# remote_V0_04.net
KiCad netlist of a schematic drawn in EAGLE
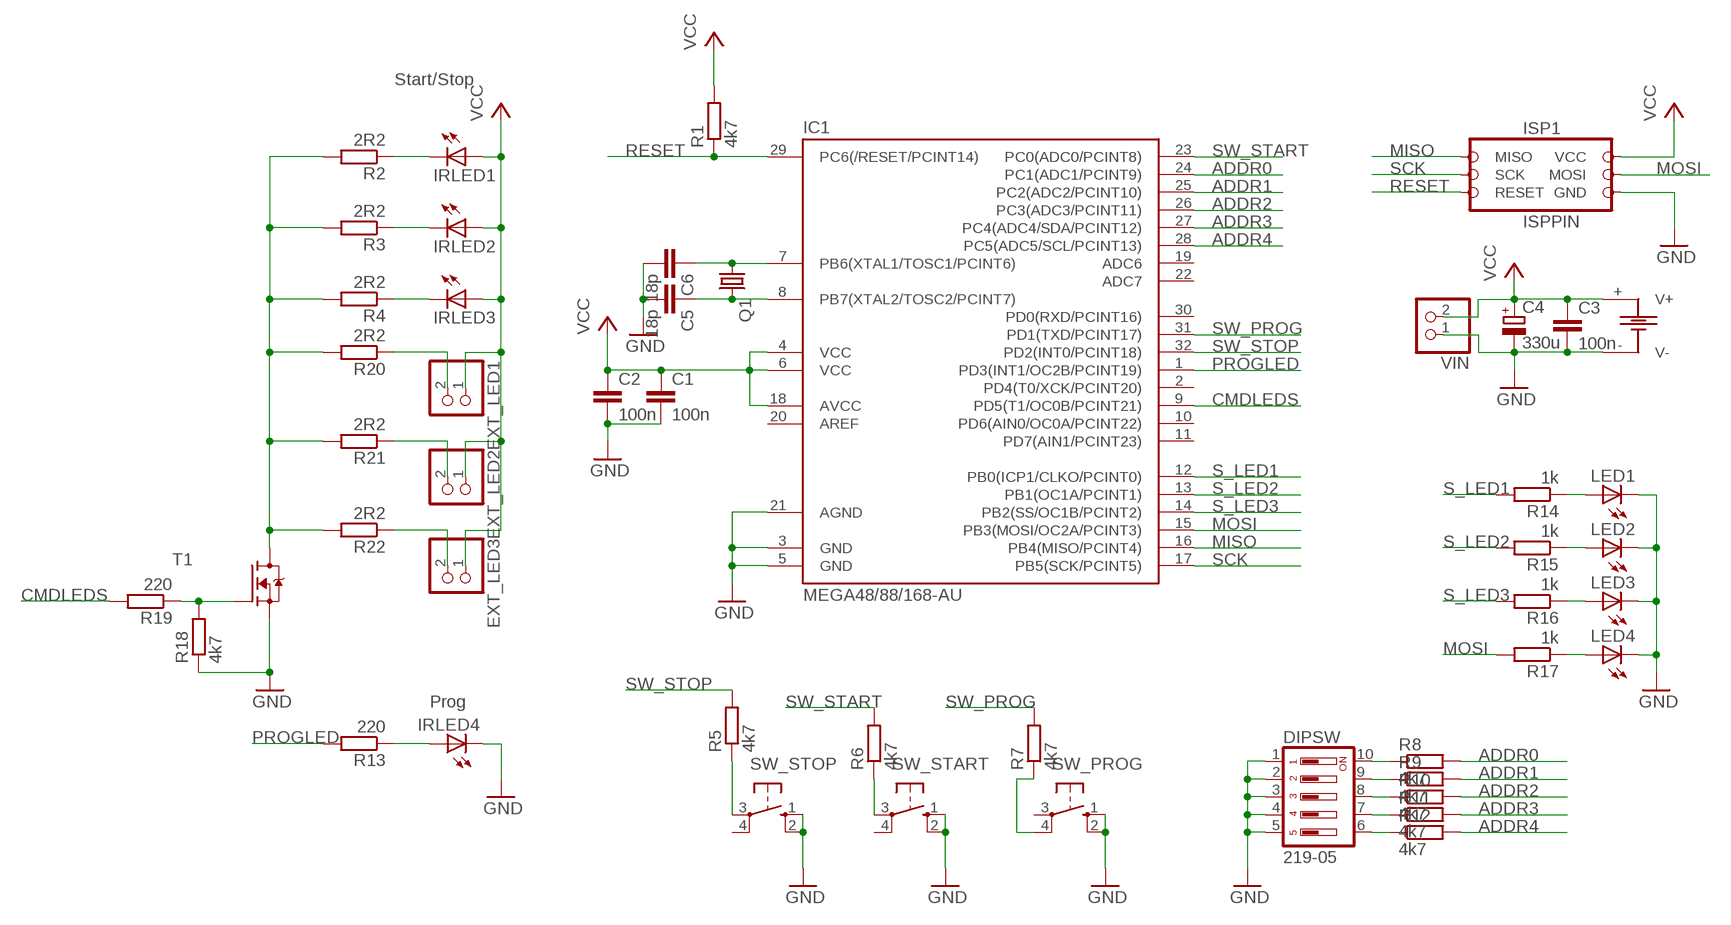
[diagram p0: schematic, sheet 1]

(export (version "E")
  (design (tool "Eeschema 10.0.6"))
  (components
    (comp (ref "B1")
      (value "BATTERY_HOLDER_1")
      (footprint "eagle-import:BAT_HOLDER_1")
      (libsource (lib "eagle-import") (part "BATTERY_HOLDER_1"))
    )
    (comp (ref "C1")
      (value "100n")
      (footprint "eagle-import:C0805WP")
      (libsource (lib "eagle-import") (part "C-EUC0805WP"))
    )
    (comp (ref "C2")
      (value "100n")
      (footprint "eagle-import:C0805WP")
      (libsource (lib "eagle-import") (part "C-EUC0805WP"))
    )
    (comp (ref "C3")
      (value "100n")
      (footprint "eagle-import:C0805WP")
      (libsource (lib "eagle-import") (part "C-EUC0805WP"))
    )
    (comp (ref "C4")
      (value "330u")
      (footprint "eagle-import:SANYO-OSCON_SMD_C6")
      (libsource (lib "eagle-import") (part "CPOL-EUSANYO_SMD_C6"))
    )
    (comp (ref "C5")
      (value "18p")
      (footprint "eagle-import:C0805WP")
      (libsource (lib "eagle-import") (part "C-EUC0805WP"))
    )
    (comp (ref "C6")
      (value "18p")
      (footprint "eagle-import:C0805WP")
      (libsource (lib "eagle-import") (part "C-EUC0805WP"))
    )
    (comp (ref "DIPSW")
      (value "219-05")
      (footprint "eagle-import:CTS-219-05")
      (libsource (lib "eagle-import") (part "219-05"))
    )
    (comp (ref "EXT_LED1")
      (value "PINHD-1X2LONG")
      (footprint "eagle-import:1X2LONG")
      (libsource (lib "eagle-import") (part "PINHD-1X2LONG"))
    )
    (comp (ref "EXT_LED2")
      (value "PINHD-1X2LONG")
      (footprint "eagle-import:1X2LONG")
      (libsource (lib "eagle-import") (part "PINHD-1X2LONG"))
    )
    (comp (ref "EXT_LED3")
      (value "PINHD-1X2LONG")
      (footprint "eagle-import:1X2LONG")
      (libsource (lib "eagle-import") (part "PINHD-1X2LONG"))
    )
    (comp (ref "IC1")
      (value "MEGA48/88/168-AU")
      (footprint "eagle-import:TQFP32-08")
      (libsource (lib "eagle-import") (part "MEGA48/88/168-AU"))
    )
    (comp (ref "IRLED1")
      (value "LEDLED5MMH")
      (footprint "eagle-import:LED5MMH")
      (libsource (lib "eagle-import") (part "LEDLED5MMH"))
    )
    (comp (ref "IRLED2")
      (value "LEDLED5MMH")
      (footprint "eagle-import:LED5MMH")
      (libsource (lib "eagle-import") (part "LEDLED5MMH"))
    )
    (comp (ref "IRLED3")
      (value "LEDLED5MMH")
      (footprint "eagle-import:LED5MMH")
      (libsource (lib "eagle-import") (part "LEDLED5MMH"))
    )
    (comp (ref "IRLED4")
      (value "LEDLED5MMH")
      (footprint "eagle-import:LED5MMH")
      (libsource (lib "eagle-import") (part "LEDLED5MMH"))
    )
    (comp (ref "ISP1")
      (value "ISPPIN")
      (footprint "eagle-import:2X03")
      (libsource (lib "eagle-import") (part "ISPPIN"))
    )
    (comp (ref "LED1")
      (value "LED0805")
      (footprint "eagle-import:LED_0805")
      (libsource (lib "eagle-import") (part "LED0805"))
    )
    (comp (ref "LED2")
      (value "LED0805")
      (footprint "eagle-import:LED_0805")
      (libsource (lib "eagle-import") (part "LED0805"))
    )
    (comp (ref "LED3")
      (value "LED0805")
      (footprint "eagle-import:LED_0805")
      (libsource (lib "eagle-import") (part "LED0805"))
    )
    (comp (ref "LED4")
      (value "LED0805")
      (footprint "eagle-import:LED_0805")
      (libsource (lib "eagle-import") (part "LED0805"))
    )
    (comp (ref "Q1")
      (value "CRYSTALHC49S")
      (footprint "eagle-import:HC49_S")
      (libsource (lib "eagle-import") (part "CRYSTALHC49S"))
    )
    (comp (ref "R1")
      (value "4k7")
      (footprint "eagle-import:R0805WP")
      (libsource (lib "eagle-import") (part "R-EU_R0805WP"))
    )
    (comp (ref "R2")
      (value "2R2")
      (footprint "eagle-import:R0805WP")
      (libsource (lib "eagle-import") (part "R-EU_R0805WP"))
    )
    (comp (ref "R3")
      (value "2R2")
      (footprint "eagle-import:R0805WP")
      (libsource (lib "eagle-import") (part "R-EU_R0805WP"))
    )
    (comp (ref "R4")
      (value "2R2")
      (footprint "eagle-import:R0805WP")
      (libsource (lib "eagle-import") (part "R-EU_R0805WP"))
    )
    (comp (ref "R5")
      (value "4k7")
      (footprint "eagle-import:R0805WP")
      (libsource (lib "eagle-import") (part "R-EU_R0805WP"))
    )
    (comp (ref "R6")
      (value "4k7")
      (footprint "eagle-import:R0805WP")
      (libsource (lib "eagle-import") (part "R-EU_R0805WP"))
    )
    (comp (ref "R7")
      (value "4k7")
      (footprint "eagle-import:R0805WP")
      (libsource (lib "eagle-import") (part "R-EU_R0805WP"))
    )
    (comp (ref "R8")
      (value "4k7")
      (footprint "eagle-import:R0805WP")
      (libsource (lib "eagle-import") (part "R-EU_R0805WP"))
    )
    (comp (ref "R9")
      (value "4k7")
      (footprint "eagle-import:R0805WP")
      (libsource (lib "eagle-import") (part "R-EU_R0805WP"))
    )
    (comp (ref "R10")
      (value "4k7")
      (footprint "eagle-import:R0805WP")
      (libsource (lib "eagle-import") (part "R-EU_R0805WP"))
    )
    (comp (ref "R11")
      (value "4k7")
      (footprint "eagle-import:R0805WP")
      (libsource (lib "eagle-import") (part "R-EU_R0805WP"))
    )
    (comp (ref "R12")
      (value "4k7")
      (footprint "eagle-import:R0805WP")
      (libsource (lib "eagle-import") (part "R-EU_R0805WP"))
    )
    (comp (ref "R13")
      (value "220")
      (footprint "eagle-import:R0805WP")
      (libsource (lib "eagle-import") (part "R-EU_R0805WP"))
    )
    (comp (ref "R14")
      (value "1k")
      (footprint "eagle-import:R0805WP")
      (libsource (lib "eagle-import") (part "R-EU_R0805WP"))
    )
    (comp (ref "R15")
      (value "1k")
      (footprint "eagle-import:R0805WP")
      (libsource (lib "eagle-import") (part "R-EU_R0805WP"))
    )
    (comp (ref "R16")
      (value "1k")
      (footprint "eagle-import:R0805WP")
      (libsource (lib "eagle-import") (part "R-EU_R0805WP"))
    )
    (comp (ref "R17")
      (value "1k")
      (footprint "eagle-import:R0805WP")
      (libsource (lib "eagle-import") (part "R-EU_R0805WP"))
    )
    (comp (ref "R18")
      (value "4k7")
      (footprint "eagle-import:R0805WP")
      (libsource (lib "eagle-import") (part "R-EU_R0805WP"))
    )
    (comp (ref "R19")
      (value "220")
      (footprint "eagle-import:R0805WP")
      (libsource (lib "eagle-import") (part "R-EU_R0805WP"))
    )
    (comp (ref "R20")
      (value "2R2")
      (footprint "eagle-import:R0805WP")
      (libsource (lib "eagle-import") (part "R-EU_R0805WP"))
    )
    (comp (ref "R21")
      (value "2R2")
      (footprint "eagle-import:R0805WP")
      (libsource (lib "eagle-import") (part "R-EU_R0805WP"))
    )
    (comp (ref "R22")
      (value "2R2")
      (footprint "eagle-import:R0805WP")
      (libsource (lib "eagle-import") (part "R-EU_R0805WP"))
    )
    (comp (ref "SW_PROG")
      (value "10-XX")
      (footprint "eagle-import:B3F-10XX")
      (fields (field (name "MPN") "B3F-1000"))
      (libsource (lib "eagle-import") (part "10-XX"))
    )
    (comp (ref "SW_START")
      (value "10-XX")
      (footprint "eagle-import:B3F-10XX")
      (fields (field (name "MPN") "B3F-1000"))
      (libsource (lib "eagle-import") (part "10-XX"))
    )
    (comp (ref "SW_STOP")
      (value "10-XX")
      (footprint "eagle-import:B3F-10XX")
      (fields (field (name "MPN") "B3F-1000"))
      (libsource (lib "eagle-import") (part "10-XX"))
    )
    (comp (ref "T1")
      (value "MOSFET_N_SOT23")
      (footprint "eagle-import:SOT23")
      (libsource (lib "eagle-import") (part "MOSFET_N_SOT23"))
    )
    (comp (ref "VIN")
      (value "PINHD-1X2")
      (footprint "eagle-import:1X02")
      (libsource (lib "eagle-import") (part "pinhead_PINHD-1X2"))
    )
  )
  (nets
    (net (code "1") (name "/ADDR0") (class "Default")
      (node (ref "IC1") (pin "24") (pinfunction "PC1(ADC1/PCINT9)_24") (pintype "bidirectional"))
      (node (ref "R8") (pin "2") (pinfunction "2_2") (pintype "passive"))
    )
    (net (code "2") (name "/ADDR1") (class "Default")
      (node (ref "IC1") (pin "25") (pinfunction "PC2(ADC2/PCINT10)_25") (pintype "bidirectional"))
      (node (ref "R9") (pin "2") (pinfunction "2_2") (pintype "passive"))
    )
    (net (code "3") (name "/ADDR2") (class "Default")
      (node (ref "IC1") (pin "26") (pinfunction "PC3(ADC3/PCINT11)_26") (pintype "bidirectional"))
      (node (ref "R10") (pin "2") (pinfunction "2_2") (pintype "passive"))
    )
    (net (code "4") (name "/ADDR3") (class "Default")
      (node (ref "IC1") (pin "27") (pinfunction "PC4(ADC4/SDA/PCINT12)_27") (pintype "bidirectional"))
      (node (ref "R11") (pin "2") (pinfunction "2_2") (pintype "passive"))
    )
    (net (code "5") (name "/ADDR4") (class "Default")
      (node (ref "IC1") (pin "28") (pinfunction "PC5(ADC5/SCL/PCINT13)_28") (pintype "bidirectional"))
      (node (ref "R12") (pin "2") (pinfunction "2_2") (pintype "passive"))
    )
    (net (code "6") (name "/CMDLEDS") (class "Default")
      (node (ref "IC1") (pin "9") (pinfunction "PD5(T1/OC0B/PCINT21)_9") (pintype "bidirectional"))
      (node (ref "R19") (pin "2") (pinfunction "2_2") (pintype "passive"))
    )
    (net (code "7") (name "/MISO") (class "Default")
      (node (ref "IC1") (pin "16") (pinfunction "PB4(MISO/PCINT4)_16") (pintype "bidirectional"))
      (node (ref "ISP1") (pin "1") (pinfunction "MISO_1") (pintype "passive"))
    )
    (net (code "8") (name "/MOSI") (class "Default")
      (node (ref "IC1") (pin "15") (pinfunction "PB3(MOSI/OC2A/PCINT3)_15") (pintype "bidirectional"))
      (node (ref "ISP1") (pin "4") (pinfunction "MOSI_4") (pintype "passive"))
      (node (ref "R17") (pin "2") (pinfunction "2_2") (pintype "passive"))
    )
    (net (code "9") (name "/PROGLED") (class "Default")
      (node (ref "IC1") (pin "1") (pinfunction "PD3(INT1/OC2B/PCINT19)_1") (pintype "bidirectional"))
      (node (ref "R13") (pin "2") (pinfunction "2_2") (pintype "passive"))
    )
    (net (code "10") (name "/RESET") (class "Default")
      (node (ref "IC1") (pin "29") (pinfunction "PC6(/RESET/PCINT14)_29") (pintype "bidirectional"))
      (node (ref "ISP1") (pin "5") (pinfunction "RESET_5") (pintype "passive"))
      (node (ref "R1") (pin "1") (pinfunction "1_1") (pintype "passive"))
    )
    (net (code "11") (name "/SCK") (class "Default")
      (node (ref "IC1") (pin "17") (pinfunction "PB5(SCK/PCINT5)_17") (pintype "bidirectional"))
      (node (ref "ISP1") (pin "3") (pinfunction "SCK_3") (pintype "passive"))
    )
    (net (code "12") (name "/SW_PROG") (class "Default")
      (node (ref "IC1") (pin "31") (pinfunction "PD1(TXD/PCINT17)_31") (pintype "bidirectional"))
      (node (ref "R7") (pin "2") (pinfunction "2_2") (pintype "passive"))
    )
    (net (code "13") (name "/SW_START") (class "Default")
      (node (ref "IC1") (pin "23") (pinfunction "PC0(ADC0/PCINT8)_23") (pintype "bidirectional"))
      (node (ref "R6") (pin "2") (pinfunction "2_2") (pintype "passive"))
    )
    (net (code "14") (name "/SW_STOP") (class "Default")
      (node (ref "IC1") (pin "32") (pinfunction "PD2(INT0/PCINT18)_32") (pintype "bidirectional"))
      (node (ref "R5") (pin "2") (pinfunction "2_2") (pintype "passive"))
    )
    (net (code "15") (name "/S_LED1") (class "Default")
      (node (ref "IC1") (pin "12") (pinfunction "PB0(ICP1/CLKO/PCINT0)_12") (pintype "bidirectional"))
      (node (ref "R14") (pin "2") (pinfunction "2_2") (pintype "passive"))
    )
    (net (code "16") (name "/S_LED2") (class "Default")
      (node (ref "IC1") (pin "13") (pinfunction "PB1(OC1A/PCINT1)_13") (pintype "bidirectional"))
      (node (ref "R15") (pin "2") (pinfunction "2_2") (pintype "passive"))
    )
    (net (code "17") (name "/S_LED3") (class "Default")
      (node (ref "IC1") (pin "14") (pinfunction "PB2(SS/OC1B/PCINT2)_14") (pintype "bidirectional"))
      (node (ref "R16") (pin "2") (pinfunction "2_2") (pintype "passive"))
    )
    (net (code "18") (name "GND") (class "Default")
      (node (ref "B1") (pin "-") (pinfunction "V-_-") (pintype "power_in"))
      (node (ref "C1") (pin "2") (pinfunction "2_2") (pintype "passive"))
      (node (ref "C2") (pin "2") (pinfunction "2_2") (pintype "passive"))
      (node (ref "C3") (pin "2") (pinfunction "2_2") (pintype "passive"))
      (node (ref "C4") (pin "-") (pinfunction "-_-") (pintype "passive"))
      (node (ref "C5") (pin "2") (pinfunction "2_2") (pintype "passive"))
      (node (ref "C6") (pin "2") (pinfunction "2_2") (pintype "passive"))
      (node (ref "DIPSW") (pin "1") (pinfunction "1_1") (pintype "passive"))
      (node (ref "DIPSW") (pin "2") (pinfunction "2_2") (pintype "passive"))
      (node (ref "DIPSW") (pin "3") (pinfunction "3_3") (pintype "passive"))
      (node (ref "DIPSW") (pin "4") (pinfunction "4_4") (pintype "passive"))
      (node (ref "DIPSW") (pin "5") (pinfunction "5_5") (pintype "passive"))
      (node (ref "IC1") (pin "21") (pinfunction "AGND_21") (pintype "power_in"))
      (node (ref "IC1") (pin "3") (pinfunction "GND_3") (pintype "power_in"))
      (node (ref "IC1") (pin "5") (pinfunction "GND_5") (pintype "power_in"))
      (node (ref "IRLED4") (pin "P$2") (pinfunction "C_P$2") (pintype "passive"))
      (node (ref "ISP1") (pin "6") (pinfunction "GND_6") (pintype "passive"))
      (node (ref "LED1") (pin "C") (pinfunction "C_C") (pintype "passive"))
      (node (ref "LED2") (pin "C") (pinfunction "C_C") (pintype "passive"))
      (node (ref "LED3") (pin "C") (pinfunction "C_C") (pintype "passive"))
      (node (ref "LED4") (pin "C") (pinfunction "C_C") (pintype "passive"))
      (node (ref "R18") (pin "1") (pinfunction "1_1") (pintype "passive"))
      (node (ref "SW_PROG") (pin "1") (pinfunction "S_1") (pintype "passive"))
      (node (ref "SW_PROG") (pin "2") (pinfunction "S1_2") (pintype "passive"))
      (node (ref "SW_START") (pin "1") (pinfunction "S_1") (pintype "passive"))
      (node (ref "SW_START") (pin "2") (pinfunction "S1_2") (pintype "passive"))
      (node (ref "SW_STOP") (pin "1") (pinfunction "S_1") (pintype "passive"))
      (node (ref "SW_STOP") (pin "2") (pinfunction "S1_2") (pintype "passive"))
      (node (ref "T1") (pin "2") (pinfunction "S_2") (pintype "passive"))
      (node (ref "VIN") (pin "1") (pinfunction "1_1") (pintype "passive"))
    )
    (net (code "19") (name "Net-(DIPSW-Pad6)") (class "Default")
      (node (ref "DIPSW") (pin "6") (pinfunction "6_6") (pintype "passive"))
      (node (ref "R12") (pin "1") (pinfunction "1_1") (pintype "passive"))
    )
    (net (code "20") (name "Net-(DIPSW-Pad7)") (class "Default")
      (node (ref "DIPSW") (pin "7") (pinfunction "7_7") (pintype "passive"))
      (node (ref "R11") (pin "1") (pinfunction "1_1") (pintype "passive"))
    )
    (net (code "21") (name "Net-(DIPSW-Pad8)") (class "Default")
      (node (ref "DIPSW") (pin "8") (pinfunction "8_8") (pintype "passive"))
      (node (ref "R10") (pin "1") (pinfunction "1_1") (pintype "passive"))
    )
    (net (code "22") (name "Net-(DIPSW-Pad9)") (class "Default")
      (node (ref "DIPSW") (pin "9") (pinfunction "9_9") (pintype "passive"))
      (node (ref "R9") (pin "1") (pinfunction "1_1") (pintype "passive"))
    )
    (net (code "23") (name "Net-(DIPSW-Pad10)") (class "Default")
      (node (ref "DIPSW") (pin "10") (pinfunction "10_10") (pintype "passive"))
      (node (ref "R8") (pin "1") (pinfunction "1_1") (pintype "passive"))
    )
    (net (code "24") (name "Net-(EXT_LED1-Pad2)") (class "Default")
      (node (ref "EXT_LED1") (pin "2") (pinfunction "2_2") (pintype "passive"))
      (node (ref "R20") (pin "1") (pinfunction "1_1") (pintype "passive"))
    )
    (net (code "25") (name "Net-(EXT_LED2-Pad2)") (class "Default")
      (node (ref "EXT_LED2") (pin "2") (pinfunction "2_2") (pintype "passive"))
      (node (ref "R21") (pin "1") (pinfunction "1_1") (pintype "passive"))
    )
    (net (code "26") (name "Net-(EXT_LED3-Pad2)") (class "Default")
      (node (ref "EXT_LED3") (pin "2") (pinfunction "2_2") (pintype "passive"))
      (node (ref "R22") (pin "1") (pinfunction "1_1") (pintype "passive"))
    )
    (net (code "27") (name "Net-(IC1-PB6(XTAL1{slash}TOSC1{slash}PCINT6))") (class "Default")
      (node (ref "C6") (pin "1") (pinfunction "1_1") (pintype "passive"))
      (node (ref "IC1") (pin "7") (pinfunction "PB6(XTAL1/TOSC1/PCINT6)_7") (pintype "bidirectional"))
      (node (ref "Q1") (pin "1") (pinfunction "1_1") (pintype "passive"))
    )
    (net (code "28") (name "Net-(IC1-PB7(XTAL2{slash}TOSC2{slash}PCINT7))") (class "Default")
      (node (ref "C5") (pin "1") (pinfunction "1_1") (pintype "passive"))
      (node (ref "IC1") (pin "8") (pinfunction "PB7(XTAL2/TOSC2/PCINT7)_8") (pintype "bidirectional"))
      (node (ref "Q1") (pin "2") (pinfunction "2_2") (pintype "passive"))
    )
    (net (code "29") (name "Net-(IRLED1-C)") (class "Default")
      (node (ref "IRLED1") (pin "P$2") (pinfunction "C_P$2") (pintype "passive"))
      (node (ref "R2") (pin "1") (pinfunction "1_1") (pintype "passive"))
    )
    (net (code "30") (name "Net-(IRLED2-C)") (class "Default")
      (node (ref "IRLED2") (pin "P$2") (pinfunction "C_P$2") (pintype "passive"))
      (node (ref "R3") (pin "1") (pinfunction "1_1") (pintype "passive"))
    )
    (net (code "31") (name "Net-(IRLED3-C)") (class "Default")
      (node (ref "IRLED3") (pin "P$2") (pinfunction "C_P$2") (pintype "passive"))
      (node (ref "R4") (pin "1") (pinfunction "1_1") (pintype "passive"))
    )
    (net (code "32") (name "Net-(IRLED4-A)") (class "Default")
      (node (ref "IRLED4") (pin "P$1") (pinfunction "A_P$1") (pintype "passive"))
      (node (ref "R13") (pin "1") (pinfunction "1_1") (pintype "passive"))
    )
    (net (code "33") (name "Net-(LED1-PadA)") (class "Default")
      (node (ref "LED1") (pin "A") (pinfunction "A_A") (pintype "passive"))
      (node (ref "R14") (pin "1") (pinfunction "1_1") (pintype "passive"))
    )
    (net (code "34") (name "Net-(LED2-PadA)") (class "Default")
      (node (ref "LED2") (pin "A") (pinfunction "A_A") (pintype "passive"))
      (node (ref "R15") (pin "1") (pinfunction "1_1") (pintype "passive"))
    )
    (net (code "35") (name "Net-(LED3-PadA)") (class "Default")
      (node (ref "LED3") (pin "A") (pinfunction "A_A") (pintype "passive"))
      (node (ref "R16") (pin "1") (pinfunction "1_1") (pintype "passive"))
    )
    (net (code "36") (name "Net-(LED4-PadA)") (class "Default")
      (node (ref "LED4") (pin "A") (pinfunction "A_A") (pintype "passive"))
      (node (ref "R17") (pin "1") (pinfunction "1_1") (pintype "passive"))
    )
    (net (code "37") (name "Net-(SW_PROG-P1)") (class "Default")
      (node (ref "R7") (pin "1") (pinfunction "1_1") (pintype "passive"))
      (node (ref "SW_PROG") (pin "4") (pinfunction "P1_4") (pintype "passive"))
    )
    (net (code "38") (name "Net-(SW_START-P)") (class "Default")
      (node (ref "R6") (pin "1") (pinfunction "1_1") (pintype "passive"))
      (node (ref "SW_START") (pin "3") (pinfunction "P_3") (pintype "passive"))
    )
    (net (code "39") (name "Net-(SW_STOP-P)") (class "Default")
      (node (ref "R5") (pin "1") (pinfunction "1_1") (pintype "passive"))
      (node (ref "SW_STOP") (pin "3") (pinfunction "P_3") (pintype "passive"))
    )
    (net (code "40") (name "Net-(T1-D)") (class "Default")
      (node (ref "R2") (pin "2") (pinfunction "2_2") (pintype "passive"))
      (node (ref "R20") (pin "2") (pinfunction "2_2") (pintype "passive"))
      (node (ref "R21") (pin "2") (pinfunction "2_2") (pintype "passive"))
      (node (ref "R22") (pin "2") (pinfunction "2_2") (pintype "passive"))
      (node (ref "R3") (pin "2") (pinfunction "2_2") (pintype "passive"))
      (node (ref "R4") (pin "2") (pinfunction "2_2") (pintype "passive"))
      (node (ref "T1") (pin "3") (pinfunction "D_3") (pintype "passive"))
    )
    (net (code "41") (name "Net-(T1-G)") (class "Default")
      (node (ref "R18") (pin "2") (pinfunction "2_2") (pintype "passive"))
      (node (ref "R19") (pin "1") (pinfunction "1_1") (pintype "passive"))
      (node (ref "T1") (pin "1") (pinfunction "G_1") (pintype "passive"))
    )
    (net (code "42") (name "VCC") (class "Default")
      (node (ref "B1") (pin "+") (pinfunction "V+_+") (pintype "power_in"))
      (node (ref "C1") (pin "1") (pinfunction "1_1") (pintype "passive"))
      (node (ref "C2") (pin "1") (pinfunction "1_1") (pintype "passive"))
      (node (ref "C3") (pin "1") (pinfunction "1_1") (pintype "passive"))
      (node (ref "C4") (pin "+") (pinfunction "+_+") (pintype "passive"))
      (node (ref "EXT_LED1") (pin "1") (pinfunction "1_1") (pintype "passive"))
      (node (ref "EXT_LED2") (pin "1") (pinfunction "1_1") (pintype "passive"))
      (node (ref "EXT_LED3") (pin "1") (pinfunction "1_1") (pintype "passive"))
      (node (ref "IC1") (pin "18") (pinfunction "AVCC_18") (pintype "passive"))
      (node (ref "IC1") (pin "4") (pinfunction "VCC_4") (pintype "power_in"))
      (node (ref "IC1") (pin "6") (pinfunction "VCC_6") (pintype "power_in"))
      (node (ref "IRLED1") (pin "P$1") (pinfunction "A_P$1") (pintype "passive"))
      (node (ref "IRLED2") (pin "P$1") (pinfunction "A_P$1") (pintype "passive"))
      (node (ref "IRLED3") (pin "P$1") (pinfunction "A_P$1") (pintype "passive"))
      (node (ref "ISP1") (pin "2") (pinfunction "VCC_2") (pintype "passive"))
      (node (ref "R1") (pin "2") (pinfunction "2_2") (pintype "passive"))
      (node (ref "VIN") (pin "2") (pinfunction "2_2") (pintype "passive"))
    )
    (net (code "43") (name "unconnected-(IC1-ADC6-Pad19)") (class "Default")
      (node (ref "IC1") (pin "19") (pinfunction "ADC6_19") (pintype "passive"))
    )
    (net (code "44") (name "unconnected-(IC1-ADC7-Pad22)") (class "Default")
      (node (ref "IC1") (pin "22") (pinfunction "ADC7_22") (pintype "passive"))
    )
    (net (code "45") (name "unconnected-(IC1-AREF-Pad20)") (class "Default")
      (node (ref "IC1") (pin "20") (pinfunction "AREF_20") (pintype "passive"))
    )
    (net (code "46") (name "unconnected-(IC1-PD0(RXD{slash}PCINT16)-Pad30)") (class "Default")
      (node (ref "IC1") (pin "30") (pinfunction "PD0(RXD/PCINT16)_30") (pintype "bidirectional"))
    )
    (net (code "47") (name "unconnected-(IC1-PD4(T0{slash}XCK{slash}PCINT20)-Pad2)") (class "Default")
      (node (ref "IC1") (pin "2") (pinfunction "PD4(T0/XCK/PCINT20)_2") (pintype "bidirectional"))
    )
    (net (code "48") (name "unconnected-(IC1-PD6(AIN0{slash}OC0A{slash}PCINT22)-Pad10)") (class "Default")
      (node (ref "IC1") (pin "10") (pinfunction "PD6(AIN0/OC0A/PCINT22)_10") (pintype "bidirectional"))
    )
    (net (code "49") (name "unconnected-(IC1-PD7(AIN1{slash}PCINT23)-Pad11)") (class "Default")
      (node (ref "IC1") (pin "11") (pinfunction "PD7(AIN1/PCINT23)_11") (pintype "bidirectional"))
    )
    (net (code "50") (name "unconnected-(SW_PROG-P-Pad3)") (class "Default")
      (node (ref "SW_PROG") (pin "3") (pinfunction "P_3") (pintype "passive"))
    )
    (net (code "51") (name "unconnected-(SW_START-P1-Pad4)") (class "Default")
      (node (ref "SW_START") (pin "4") (pinfunction "P1_4") (pintype "passive"))
    )
    (net (code "52") (name "unconnected-(SW_STOP-P1-Pad4)") (class "Default")
      (node (ref "SW_STOP") (pin "4") (pinfunction "P1_4") (pintype "passive"))
    )
  )
)
